# TOP_LEVEL.net
KiCad netlist of a schematic drawn in Altium Designer
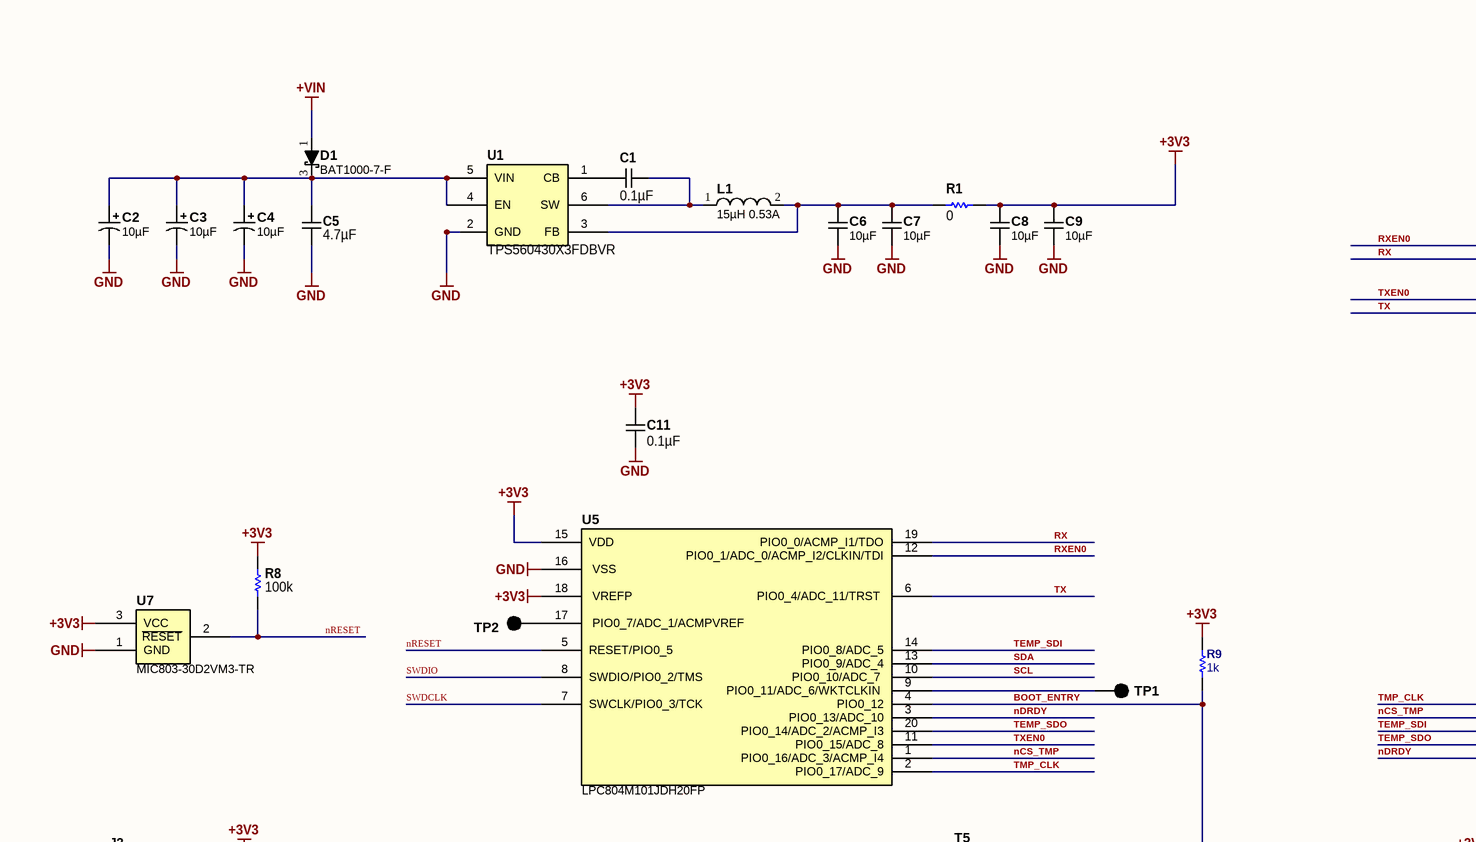
[diagram p0: TOP_LEVEL.SCHDOC, top left]
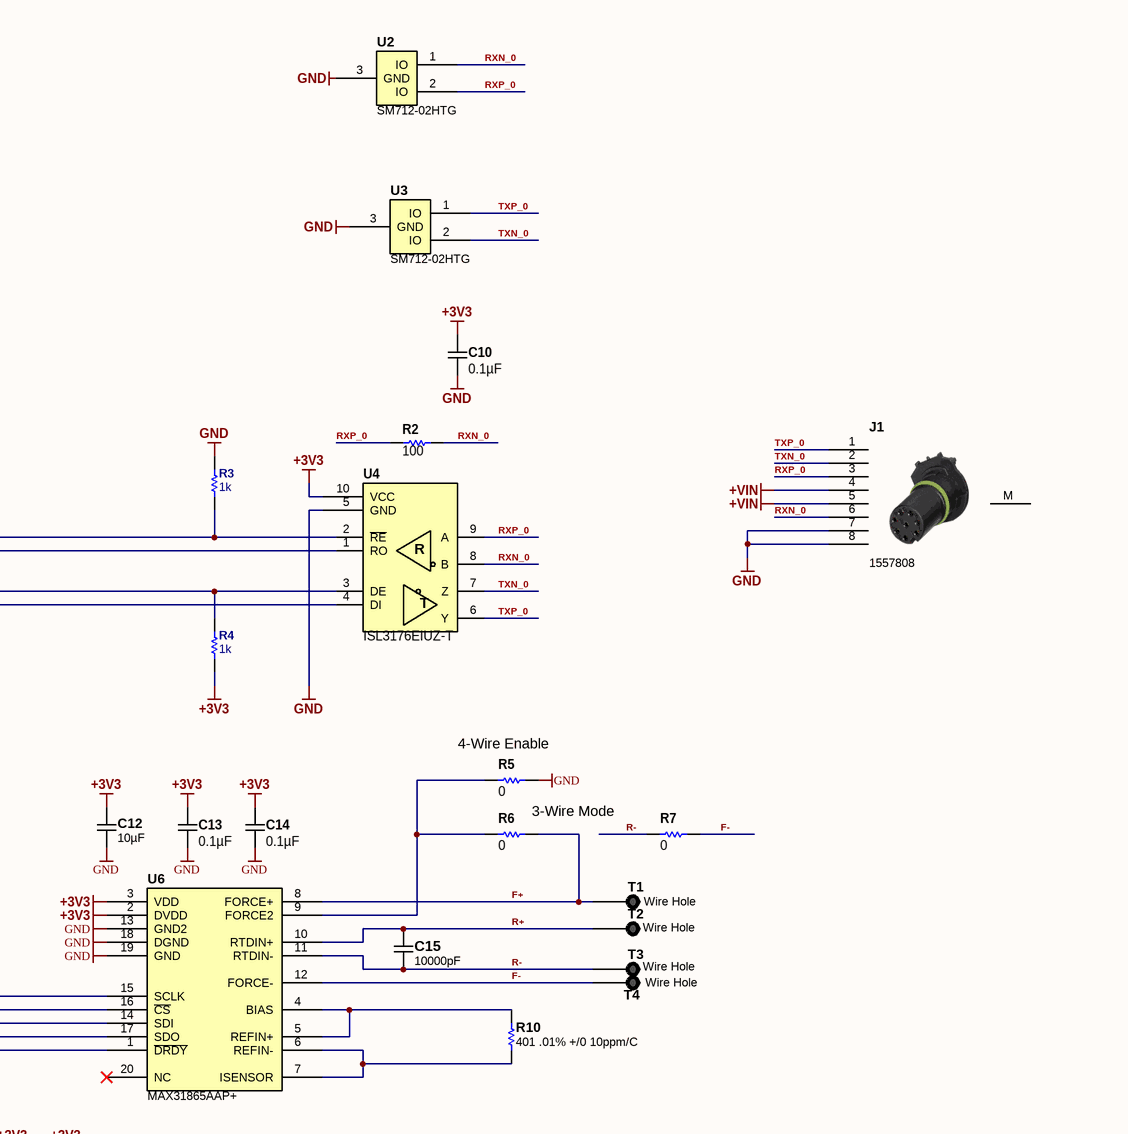
[diagram p1: TOP_LEVEL.SCHDOC, top right]
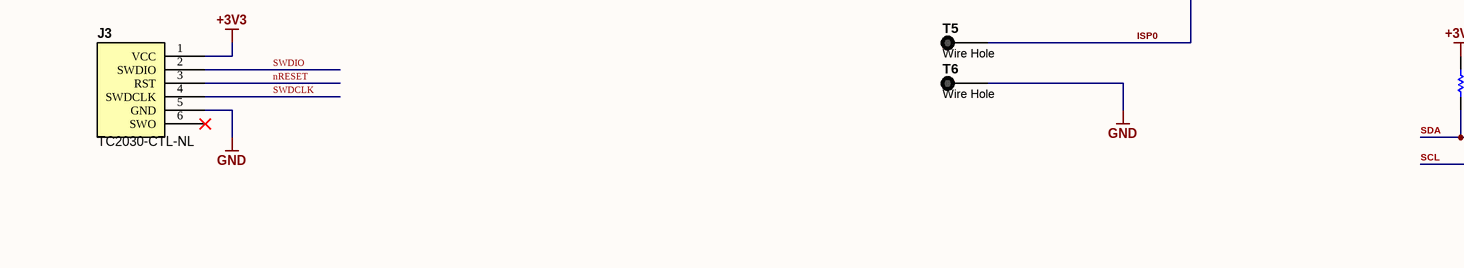
[diagram p2: TOP_LEVEL.SCHDOC, bottom left]
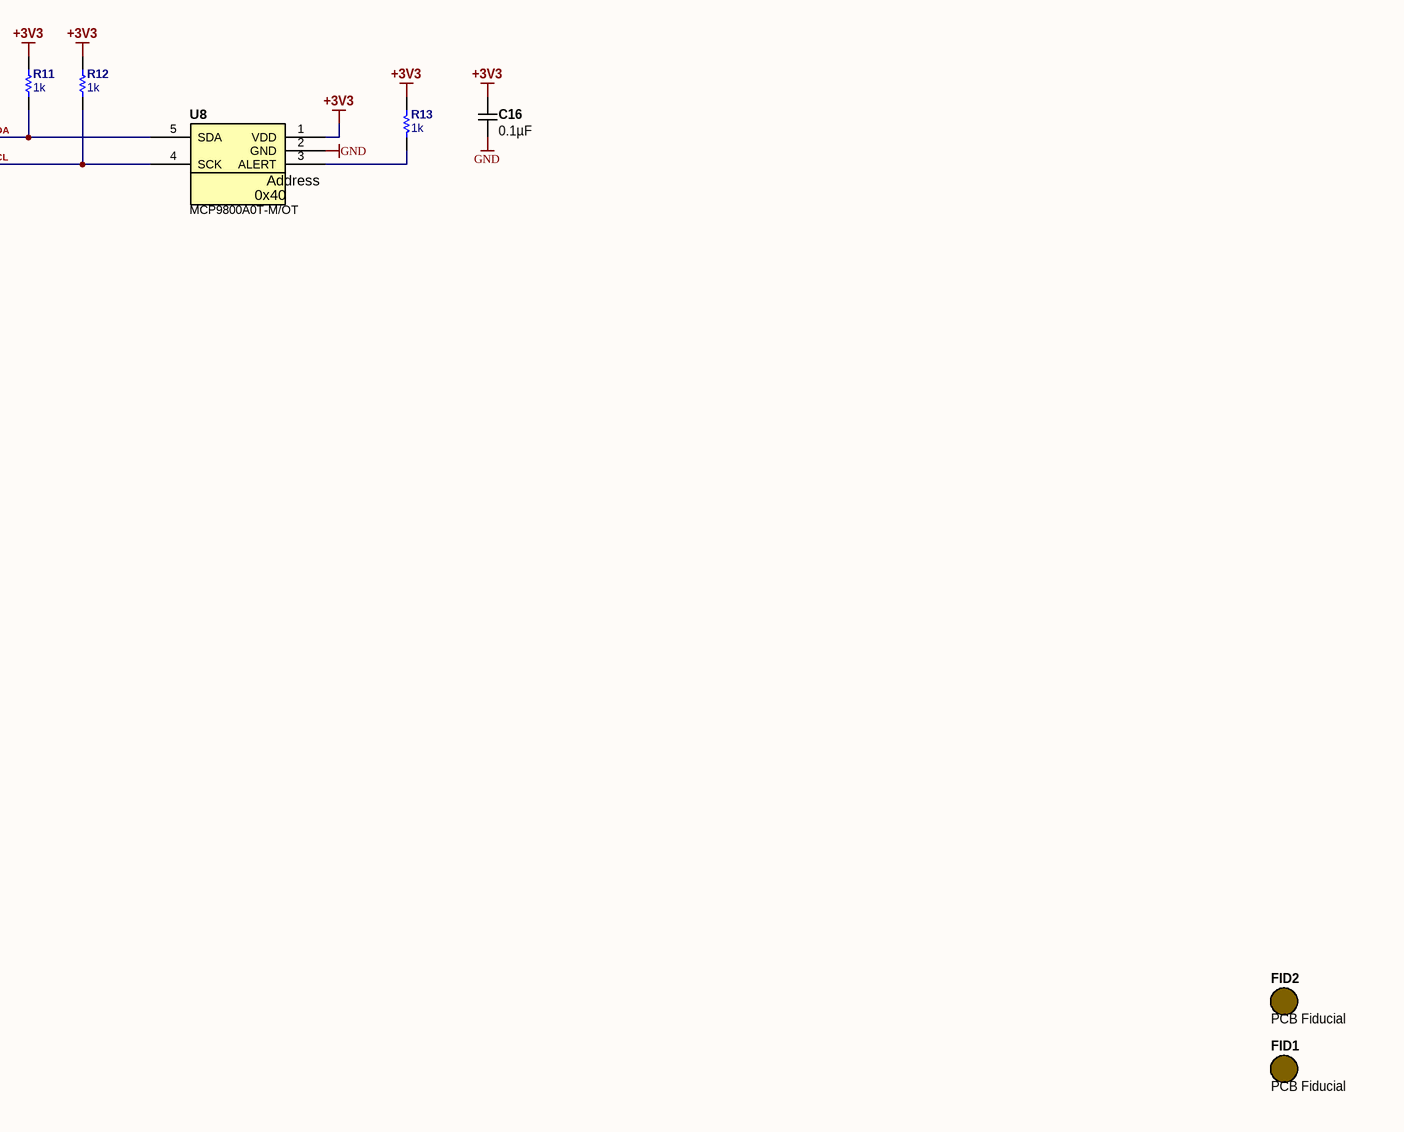
[diagram p3: TOP_LEVEL.SCHDOC, bottom right]

(export (version "E")
  (design (tool "Eeschema 10.0.6"))
  (components
    (comp (ref "C1")
      (value "0.1µF")
      (footprint "C0603_0.90MM_MD")
      (description "CAP CER 0.1UF 50V X7R 0603")
      (fields
        (field (name "MANUFACTURER PART NUMBER") "CGA3E2X7R1H104K080AE")
        (field (name "MANUFACTURER") "TDK Corporation")
      )
      (libsource (lib "Capacitors - TDK- AEC-Q200") (part "C_2P_NP"))
    )
    (comp (ref "C2")
      (value "10µF")
      (footprint "C_ALU_B")
      (description "CAP ALUM 10UF 35V 20% SMD")
      (fields
        (field (name "MANUFACTURER PART NUMBER") "EEE-FK1V100UR")
        (field (name "MANUFACTURER") "Panasonic Electronic Components")
      )
      (libsource (lib "Capacitors - Panasonic - AluminumElectrolytic - AEC-Q200") (part "C_2P_P"))
    )
    (comp (ref "C3")
      (value "10µF")
      (footprint "C_ALU_B")
      (description "CAP ALUM 10UF 35V 20% SMD")
      (fields
        (field (name "MANUFACTURER PART NUMBER") "EEE-FK1V100UR")
        (field (name "MANUFACTURER") "Panasonic Electronic Components")
      )
      (libsource (lib "Capacitors - Panasonic - AluminumElectrolytic - AEC-Q200") (part "C_2P_P"))
    )
    (comp (ref "C4")
      (value "10µF")
      (footprint "C_ALU_B")
      (description "CAP ALUM 10UF 35V 20% SMD")
      (fields
        (field (name "MANUFACTURER PART NUMBER") "EEE-FK1V100UR")
        (field (name "MANUFACTURER") "Panasonic Electronic Components")
      )
      (libsource (lib "Capacitors - Panasonic - AluminumElectrolytic - AEC-Q200") (part "C_2P_P"))
    )
    (comp (ref "C5")
      (value "4.7µF")
      (footprint "C0805_1.50MM_MD")
      (description "CAP CER 4.7UF 35V X7R 0805")
      (fields
        (field (name "MANUFACTURER PART NUMBER") "CGA4J1X7R1V475K125AE")
        (field (name "MANUFACTURER") "TDK Corporation")
      )
      (libsource (lib "Capacitors - TDK- AEC-Q200") (part "C_2P_NP"))
    )
    (comp (ref "C6")
      (value "10µF")
      (footprint "C0805_1.25MM_MD")
      (description "CAP CER 10UF 6.3V X7R 0805")
      (fields
        (field (name "MANUFACTURER PART NUMBER") "CGA4J1X7R0J106K125AD")
        (field (name "MANUFACTURER") "TDK Corporation")
      )
      (libsource (lib "Capacitors - TDK- AEC-Q200") (part "C_2P_NP"))
    )
    (comp (ref "C7")
      (value "10µF")
      (footprint "C0805_1.25MM_MD")
      (description "CAP CER 10UF 6.3V X7R 0805")
      (fields
        (field (name "MANUFACTURER PART NUMBER") "CGA4J1X7R0J106K125AD")
        (field (name "MANUFACTURER") "TDK Corporation")
      )
      (libsource (lib "Capacitors - TDK- AEC-Q200") (part "C_2P_NP"))
    )
    (comp (ref "C8")
      (value "10µF")
      (footprint "C0805_1.25MM_MD")
      (description "CAP CER 10UF 6.3V X7R 0805")
      (fields
        (field (name "MANUFACTURER PART NUMBER") "CGA4J1X7R0J106K125AD")
        (field (name "MANUFACTURER") "TDK Corporation")
      )
      (libsource (lib "Capacitors - TDK- AEC-Q200") (part "C_2P_NP"))
    )
    (comp (ref "C9")
      (value "10µF")
      (footprint "C0805_1.25MM_MD")
      (description "CAP CER 10UF 6.3V X7R 0805")
      (fields
        (field (name "MANUFACTURER PART NUMBER") "CGA4J1X7R0J106K125AD")
        (field (name "MANUFACTURER") "TDK Corporation")
      )
      (libsource (lib "Capacitors - TDK- AEC-Q200") (part "C_2P_NP"))
    )
    (comp (ref "C10")
      (value "0.1µF")
      (footprint "C0603_0.90MM_MD")
      (description "CAP CER 0.1UF 50V X7R 0603")
      (fields
        (field (name "MANUFACTURER PART NUMBER") "CGA3E2X7R1H104K080AE")
        (field (name "MANUFACTURER") "TDK Corporation")
      )
      (libsource (lib "Capacitors - TDK- AEC-Q200") (part "C_2P_NP"))
    )
    (comp (ref "C11")
      (value "0.1µF")
      (footprint "C0603_0.90MM_MD")
      (description "CAP CER 0.1UF 50V X7R 0603")
      (fields
        (field (name "MANUFACTURER PART NUMBER") "CGA3E2X7R1H104K080AE")
        (field (name "MANUFACTURER") "TDK Corporation")
      )
      (libsource (lib "Capacitors - TDK- AEC-Q200") (part "C_2P_NP"))
    )
    (comp (ref "C12")
      (value "10µF")
      (footprint "C0805_1.25MM_MD")
      (description "CAP CER 10UF 6.3V X7R 0805")
      (fields
        (field (name "MANUFACTURER PART NUMBER") "CGA4J1X7R0J106K125AD")
        (field (name "MANUFACTURER") "TDK Corporation")
      )
      (libsource (lib "Capacitors - TDK- AEC-Q200") (part "C_2P_NP"))
    )
    (comp (ref "C13")
      (value "0.1µF")
      (footprint "C0603_0.90MM_MD")
      (description "CAP CER 0.1UF 50V X7R 0603")
      (fields
        (field (name "MANUFACTURER PART NUMBER") "CGA3E2X7R1H104K080AE")
        (field (name "MANUFACTURER") "TDK Corporation")
      )
      (libsource (lib "Capacitors - TDK- AEC-Q200") (part "C_2P_NP"))
    )
    (comp (ref "C14")
      (value "0.1µF")
      (footprint "C0603_0.90MM_MD")
      (description "CAP CER 0.1UF 50V X7R 0603")
      (fields
        (field (name "MANUFACTURER PART NUMBER") "CGA3E2X7R1H104K080AE")
        (field (name "MANUFACTURER") "TDK Corporation")
      )
      (libsource (lib "Capacitors - TDK- AEC-Q200") (part "C_2P_NP"))
    )
    (comp (ref "C15")
      (value "10000pF")
      (footprint "C0603_0.90MM_HD")
      (description "CAP CER 10000PF 50V X7R 0603")
      (fields
        (field (name "MANUFACTURER PART NUMBER") "AC0603KPX7R9BB103")
        (field (name "MANUFACTURER") "Yageo")
      )
      (libsource (lib "Capacitors - Yageo - AEC-Q200") (part "C_2P_NP"))
    )
    (comp (ref "C16")
      (value "0.1µF")
      (footprint "C0603_0.90MM_MD")
      (description "CAP CER 0.1UF 50V X7R 0603")
      (fields
        (field (name "MANUFACTURER PART NUMBER") "CGA3E2X7R1H104K080AE")
        (field (name "MANUFACTURER") "TDK Corporation")
      )
      (libsource (lib "Capacitors - TDK- AEC-Q200") (part "C_2P_NP"))
    )
    (comp (ref "D1")
      (value "BAT1000-7-F")
      (footprint "D_SOT-23-3_P")
      (description "DIODE SCHOTTKY 40V 1A SOT23")
      (fields (field (name "MANUFACTURER") "Diodes Inc"))
      (libsource (lib "Diodes") (part "DS_1A_3C"))
    )
    (comp (ref "FID1")
      (value "PCB Fiducial")
      (footprint "Fiducial 1mm - 2mm")
      (libsource (lib "eFiducial") (part "Fiducial"))
    )
    (comp (ref "FID2")
      (value "PCB Fiducial")
      (footprint "Fiducial 1mm - 2mm")
      (libsource (lib "eFiducial") (part "Fiducial"))
    )
    (comp (ref "J1")
      (value "1557808")
      (footprint "1557808")
      (description "Circular Metric Connectors SACC-CI-M12FS -8CON-L180-THR")
      (fields (field (name "MANUFACTURER") "Phoenix Contact"))
      (libsource (lib "eConnector_Phoenix_M12") (part "1557808"))
    )
    (comp (ref "J3")
      (value "TC2030‐CTL‐NL")
      (footprint "TC2030")
      (description "Tag Connect Pads - No latching Clips - ARM")
      (libsource (lib "eConnector") (part "TC2030‐CTL‐NL"))
    )
    (comp (ref "L1")
      (value "15µH 0.53A")
      (footprint "L_NRH3012")
      (description "Inductor 15µH 0.53A")
      (fields
        (field (name "MANUFACTURER PART NUMBER") "NRH3012T150MN")
        (field (name "MANUFACTURER") "Taiyo Yuden")
      )
      (libsource (lib "Inductors") (part "L_2P"))
    )
    (comp (ref "R1")
      (value "0")
      (footprint "R0603_0.55MM_MD")
      (description "RES 0.0 OHM 1/10W JUMP 0603 SMD")
      (fields
        (field (name "MANUFACTURER PART NUMBER") "ERJ-3GEY0R00V")
        (field (name "MANUFACTURER") "Panasonic Electronic Components")
      )
      (libsource (lib "Resistors - Panasonic - AEC-Q200") (part "R_2P"))
    )
    (comp (ref "R2")
      (value "100")
      (footprint "R0603_0.55MM_MD")
      (description "RES 100 OHM 1/10W 1% 0603 SMD")
      (fields
        (field (name "MANUFACTURER PART NUMBER") "ERJ-3EKF1000V")
        (field (name "MANUFACTURER") "Panasonic Electronic Components")
      )
      (libsource (lib "Resistors - Panasonic - AEC-Q200") (part "R_2P"))
    )
    (comp (ref "R3")
      (value "1k")
      (footprint "R0603_0.55MM_MD")
      (description "RES 1K OHM 1/10W 1% 0603 SMD")
      (fields
        (field (name "MANUFACTURER PART NUMBER") "ERJ-3EKF1001V")
        (field (name "MANUFACTURER") "Panasonic Electronic Components")
      )
      (libsource (lib "Resistors - Panasonic - AEC-Q200") (part "R_2P"))
    )
    (comp (ref "R4")
      (value "1k")
      (footprint "R0603_0.55MM_MD")
      (description "RES 1K OHM 1/10W 1% 0603 SMD")
      (fields
        (field (name "MANUFACTURER PART NUMBER") "ERJ-3EKF1001V")
        (field (name "MANUFACTURER") "Panasonic Electronic Components")
      )
      (libsource (lib "Resistors - Panasonic - AEC-Q200") (part "R_2P"))
    )
    (comp (ref "R5")
      (value "0")
      (footprint "R0603_0.55MM_MD")
      (description "RES 0.0 OHM 1/10W JUMP 0603 SMD")
      (fields
        (field (name "MANUFACTURER PART NUMBER") "ERJ-3GEY0R00V")
        (field (name "MANUFACTURER") "Panasonic Electronic Components")
      )
      (libsource (lib "Resistors - Panasonic - AEC-Q200") (part "R_2P"))
    )
    (comp (ref "R6")
      (value "0")
      (footprint "R0603_0.55MM_MD")
      (description "RES 0.0 OHM 1/10W JUMP 0603 SMD")
      (fields
        (field (name "MANUFACTURER PART NUMBER") "ERJ-3GEY0R00V")
        (field (name "MANUFACTURER") "Panasonic Electronic Components")
      )
      (libsource (lib "Resistors - Panasonic - AEC-Q200") (part "R_2P"))
    )
    (comp (ref "R7")
      (value "0")
      (footprint "R0603_0.55MM_MD")
      (description "RES 0.0 OHM 1/10W JUMP 0603 SMD")
      (fields
        (field (name "MANUFACTURER PART NUMBER") "ERJ-3GEY0R00V")
        (field (name "MANUFACTURER") "Panasonic Electronic Components")
      )
      (libsource (lib "Resistors - Panasonic - AEC-Q200") (part "R_2P"))
    )
    (comp (ref "R8")
      (value "100k")
      (footprint "R0603_0.55MM_MD")
      (description "RES 100K OHM 1/10W 1% 0603 SMD")
      (fields
        (field (name "MANUFACTURER PART NUMBER") "ERJ-3EKF1003V")
        (field (name "MANUFACTURER") "Panasonic Electronic Components")
      )
      (libsource (lib "Resistors - Panasonic - AEC-Q200") (part "R_2P"))
    )
    (comp (ref "R9")
      (value "1k")
      (footprint "R0603_0.55MM_MD")
      (description "RES 1K OHM 1/10W 1% 0603 SMD")
      (fields
        (field (name "MANUFACTURER PART NUMBER") "ERJ-3EKF1001V")
        (field (name "MANUFACTURER") "Panasonic Electronic Components")
      )
      (libsource (lib "Resistors - Panasonic - AEC-Q200") (part "R_2P"))
    )
    (comp (ref "R10")
      (value "401 .01% +/0 10ppm/C")
      (footprint "R0603_0.55MM_MD")
      (description "402 ±0.1% 0.15W Chip Resistor 0603 (1608 Metric) Anti-Sulfur, Automotive AEC-Q200 Thin Film")
      (fields
        (field (name "MANUFACTURER") "TE Connectivity")
        (field (name "MANUFACTURER PART NUMBER") "RQ73C1J402RBTD")
      )
      (libsource (lib "eResistors") (part "RQ73C1J402RBTD"))
    )
    (comp (ref "R11")
      (value "1k")
      (footprint "R0603_0.55MM_MD")
      (description "RES 1K OHM 1/10W 1% 0603 SMD")
      (fields
        (field (name "MANUFACTURER PART NUMBER") "ERJ-3EKF1001V")
        (field (name "MANUFACTURER") "Panasonic Electronic Components")
      )
      (libsource (lib "Resistors - Panasonic - AEC-Q200") (part "R_2P"))
    )
    (comp (ref "R12")
      (value "1k")
      (footprint "R0603_0.55MM_MD")
      (description "RES 1K OHM 1/10W 1% 0603 SMD")
      (fields
        (field (name "MANUFACTURER PART NUMBER") "ERJ-3EKF1001V")
        (field (name "MANUFACTURER") "Panasonic Electronic Components")
      )
      (libsource (lib "Resistors - Panasonic - AEC-Q200") (part "R_2P"))
    )
    (comp (ref "R13")
      (value "1k")
      (footprint "R0603_0.55MM_MD")
      (description "RES 1K OHM 1/10W 1% 0603 SMD")
      (fields
        (field (name "MANUFACTURER PART NUMBER") "ERJ-3EKF1001V")
        (field (name "MANUFACTURER") "Panasonic Electronic Components")
      )
      (libsource (lib "Resistors - Panasonic - AEC-Q200") (part "R_2P"))
    )
    (comp (ref "T1")
      (value "Wire Hole")
      (footprint "SOLDER_HOLE")
      (libsource (lib "eConnector") (part "SOLDER_HOLE"))
    )
    (comp (ref "T2")
      (value "Wire Hole")
      (footprint "SOLDER_HOLE")
      (libsource (lib "eConnector") (part "SOLDER_HOLE"))
    )
    (comp (ref "T3")
      (value "Wire Hole")
      (footprint "SOLDER_HOLE")
      (libsource (lib "eConnector") (part "SOLDER_HOLE"))
    )
    (comp (ref "T4")
      (value "Wire Hole")
      (footprint "SOLDER_HOLE")
      (libsource (lib "eConnector") (part "SOLDER_HOLE"))
    )
    (comp (ref "T5")
      (value "Wire Hole")
      (footprint "SOLDER_HOLE")
      (libsource (lib "eConnector") (part "SOLDER_HOLE"))
    )
    (comp (ref "T6")
      (value "Wire Hole")
      (footprint "SOLDER_HOLE")
      (libsource (lib "eConnector") (part "SOLDER_HOLE"))
    )
    (comp (ref "TP1")
      (value "SMT_TEST")
      (footprint "SMT_TP - 35")
      (libsource (lib "eTestPoint") (part "SMT_TEST"))
    )
    (comp (ref "TP2")
      (value "SMT_TEST")
      (footprint "SMT_TP - 35")
      (libsource (lib "eTestPoint") (part "SMT_TEST"))
    )
    (comp (ref "U1")
      (value "TPS560430X3FDBVR")
      (footprint "SOT95P245X145-6L")
      (description "Buck Switching Regulator IC Positive PWM 3.3V 1 Output 600mA SOT-23-6")
      (fields (field (name "MANUFACTURER") "Texas Instruments"))
      (libsource (lib "eIC_Regulator") (part "TPS560430X3FDBVR"))
    )
    (comp (ref "U2")
      (value "SM712-02HTG")
      (footprint "SOT-23")
      (fields (field (name "MANUFACTURER") "Littelfuse"))
      (libsource (lib "eDiode") (part "SM712-02HTG"))
    )
    (comp (ref "U3")
      (value "SM712-02HTG")
      (footprint "SOT-23")
      (fields (field (name "MANUFACTURER") "Littelfuse"))
      (libsource (lib "eDiode") (part "SM712-02HTG"))
    )
    (comp (ref "U4")
      (value "ISL3176EIUZ-T")
      (footprint "10 MSOP")
      (description "IC TXRX RS422/485 20MBPS 10MSOP")
      (fields (field (name "MANUFACTURER") "Intersil"))
      (libsource (lib "eIC") (part "ISL3176EIUZ-T"))
    )
    (comp (ref "U5")
      (value "LPC804M101JDH20FP")
      (footprint "TSOP65P640X105-20N")
      (description "MCU 32-bit ARM Cortex M0+ RISC 32KB Flash 3.3V 20-Pin TSSOP Tube")
      (fields (field (name "MANUFACTURER") "NXP Semiconductors"))
      (libsource (lib "eIC") (part "LPC804M101JDH20FP"))
    )
    (comp (ref "U6")
      (value "MAX31865AAP+")
      (footprint "SOP65P780X200-20N")
      (description "Temp Monitoring System (Sensor)  External Sensor SPI Output 20-SSOP")
      (fields (field (name "MANUFACTURER") "Maxim"))
      (libsource (lib "eIC") (part "MAX31865AAP+"))
    )
    (comp (ref "U7")
      (value "MIC803-30D2VM3-TR")
      (footprint "SOT-23")
      (description "3-Pin Microprocessor Supervisor Circuit w/ Open-Drain Reset Output, 3 SOT-23 - T/R")
      (fields (field (name "MANUFACTURER") "Microchip"))
      (libsource (lib "eIC") (part "MIC803-30D2VM3-TR"))
    )
    (comp (ref "U8")
      (value "MCP9800A0T-M/OT")
      (footprint "SOT23-5")
      (description "SENSOR TEMP I2C/SMBUS SOT23-5")
      (fields (field (name "MANUFACTURER") "Microchip Technology"))
      (libsource (lib "eIC") (part "MCP9800A0T-M/OT"))
    )
  )
  (nets
    (net (code "1") (name "+3V3") (class "Default")
      (node (ref "C10") (pin "2") (pinfunction "1_2") (pintype "passive"))
      (node (ref "C11") (pin "2") (pinfunction "1_2") (pintype "passive"))
      (node (ref "C12") (pin "2") (pinfunction "1_2") (pintype "passive"))
      (node (ref "C13") (pin "2") (pinfunction "1_2") (pintype "passive"))
      (node (ref "C14") (pin "2") (pinfunction "1_2") (pintype "passive"))
      (node (ref "C16") (pin "2") (pinfunction "1_2") (pintype "passive"))
      (node (ref "C8") (pin "2") (pinfunction "1_2") (pintype "passive"))
      (node (ref "C9") (pin "2") (pinfunction "1_2") (pintype "passive"))
      (node (ref "J3") (pin "1") (pinfunction "VCC_1") (pintype "passive"))
      (node (ref "R1") (pin "2") (pinfunction "2_2") (pintype "passive"))
      (node (ref "R11") (pin "1") (pinfunction "1_1") (pintype "passive"))
      (node (ref "R12") (pin "1") (pinfunction "1_1") (pintype "passive"))
      (node (ref "R13") (pin "1") (pinfunction "1_1") (pintype "passive"))
      (node (ref "R4") (pin "2") (pinfunction "2_2") (pintype "passive"))
      (node (ref "R8") (pin "1") (pinfunction "1_1") (pintype "passive"))
      (node (ref "R9") (pin "1") (pinfunction "1_1") (pintype "passive"))
      (node (ref "U4") (pin "10") (pinfunction "VCC_10") (pintype "passive"))
      (node (ref "U5") (pin "15") (pinfunction "VDD_15") (pintype "passive"))
      (node (ref "U5") (pin "18") (pinfunction "_VREFP_18") (pintype "passive"))
      (node (ref "U6") (pin "2") (pinfunction "DVDD_2") (pintype "passive"))
      (node (ref "U6") (pin "3") (pinfunction "VDD_3") (pintype "passive"))
      (node (ref "U7") (pin "3") (pinfunction "VCC_3") (pintype "passive"))
      (node (ref "U8") (pin "1") (pinfunction "VDD_1") (pintype "passive"))
    )
    (net (code "2") (name "+VIN") (class "Default")
      (node (ref "D1") (pin "1") (pinfunction "A_1") (pintype "passive"))
      (node (ref "J1") (pin "4") (pinfunction "4_4") (pintype "passive"))
      (node (ref "J1") (pin "5") (pinfunction "5_5") (pintype "passive"))
    )
    (net (code "3") (name "/BOOT_ENTRY") (class "Default")
      (node (ref "R9") (pin "2") (pinfunction "2_2") (pintype "passive"))
      (node (ref "T5") (pin "1") (pinfunction "1_1") (pintype "passive"))
      (node (ref "U5") (pin "4") (pinfunction "PIO0_12_4") (pintype "passive"))
    )
    (net (code "4") (name "/F+") (class "Default")
      (node (ref "R6") (pin "2") (pinfunction "2_2") (pintype "passive"))
      (node (ref "T1") (pin "1") (pinfunction "1_1") (pintype "passive"))
      (node (ref "U6") (pin "8") (pinfunction "FORCE+_8") (pintype "passive"))
    )
    (net (code "5") (name "/F-") (class "Default")
      (node (ref "R7") (pin "2") (pinfunction "2_2") (pintype "passive"))
      (node (ref "T4") (pin "1") (pinfunction "1_1") (pintype "passive"))
      (node (ref "U6") (pin "12") (pinfunction "FORCE-_12") (pintype "passive"))
    )
    (net (code "6") (name "/R+") (class "Default")
      (node (ref "C15") (pin "2") (pinfunction "1_2") (pintype "passive"))
      (node (ref "T2") (pin "1") (pinfunction "1_1") (pintype "passive"))
      (node (ref "U6") (pin "10") (pinfunction "RTDIN+_10") (pintype "passive"))
    )
    (net (code "7") (name "/R-") (class "Default")
      (node (ref "C15") (pin "1") (pinfunction "1_1") (pintype "passive"))
      (node (ref "R7") (pin "1") (pinfunction "1_1") (pintype "passive"))
      (node (ref "T3") (pin "1") (pinfunction "1_1") (pintype "passive"))
      (node (ref "U6") (pin "11") (pinfunction "RTDIN-_11") (pintype "passive"))
    )
    (net (code "8") (name "/RX") (class "Default")
      (node (ref "U4") (pin "1") (pinfunction "RO_1") (pintype "passive"))
      (node (ref "U5") (pin "19") (pinfunction "_PIO0_0/ACMP_I1/TDO_19") (pintype "passive"))
    )
    (net (code "9") (name "/RXEN0") (class "Default")
      (node (ref "R3") (pin "2") (pinfunction "2_2") (pintype "passive"))
      (node (ref "U4") (pin "2") (pinfunction "~{RE}_2") (pintype "passive"))
      (node (ref "U5") (pin "12") (pinfunction "PIO0_1/ADC_0/ACMP_I2/CLKIN/TDI_12") (pintype "passive"))
    )
    (net (code "10") (name "/RXN_0") (class "Default")
      (node (ref "J1") (pin "6") (pinfunction "6_6") (pintype "passive"))
      (node (ref "R2") (pin "2") (pinfunction "2_2") (pintype "passive"))
      (node (ref "U2") (pin "1") (pinfunction "IO_1") (pintype "passive"))
      (node (ref "U4") (pin "8") (pinfunction "B_8") (pintype "passive"))
    )
    (net (code "11") (name "/RXP_0") (class "Default")
      (node (ref "J1") (pin "3") (pinfunction "3_3") (pintype "passive"))
      (node (ref "R2") (pin "1") (pinfunction "1_1") (pintype "passive"))
      (node (ref "U2") (pin "2") (pinfunction "IO_2") (pintype "passive"))
      (node (ref "U4") (pin "9") (pinfunction "A_9") (pintype "passive"))
    )
    (net (code "12") (name "/SCL") (class "Default")
      (node (ref "R12") (pin "2") (pinfunction "2_2") (pintype "passive"))
      (node (ref "U5") (pin "10") (pinfunction "PIO0_10/ADC_7_10") (pintype "passive"))
      (node (ref "U8") (pin "4") (pinfunction "SCK_4") (pintype "passive"))
    )
    (net (code "13") (name "/SDA") (class "Default")
      (node (ref "R11") (pin "2") (pinfunction "2_2") (pintype "passive"))
      (node (ref "U5") (pin "13") (pinfunction "PIO0_9/ADC_4_13") (pintype "passive"))
      (node (ref "U8") (pin "5") (pinfunction "SDA_5") (pintype "passive"))
    )
    (net (code "14") (name "/SWDCLK") (class "Default")
      (node (ref "J3") (pin "4") (pinfunction "SWDCLK_4") (pintype "passive"))
      (node (ref "U5") (pin "7") (pinfunction "SWCLK/PIO0_3/TCK_7") (pintype "passive"))
    )
    (net (code "15") (name "/SWDIO") (class "Default")
      (node (ref "J3") (pin "2") (pinfunction "SWDIO_2") (pintype "passive"))
      (node (ref "U5") (pin "8") (pinfunction "SWDIO/PIO0_2/TMS_8") (pintype "passive"))
    )
    (net (code "16") (name "/TEMP_SDI") (class "Default")
      (node (ref "U5") (pin "14") (pinfunction "PIO0_8/ADC_5_14") (pintype "passive"))
      (node (ref "U6") (pin "14") (pinfunction "SDI_14") (pintype "passive"))
    )
    (net (code "17") (name "/TEMP_SDO") (class "Default")
      (node (ref "U5") (pin "20") (pinfunction "_PIO0_14/ADC_2/ACMP_I3_20") (pintype "passive"))
      (node (ref "U6") (pin "17") (pinfunction "SDO_17") (pintype "passive"))
    )
    (net (code "18") (name "/TMP_CLK") (class "Default")
      (node (ref "U5") (pin "2") (pinfunction "PIO0_17/ADC_9_2") (pintype "passive"))
      (node (ref "U6") (pin "15") (pinfunction "SCLK_15") (pintype "passive"))
    )
    (net (code "19") (name "/TX") (class "Default")
      (node (ref "U4") (pin "4") (pinfunction "DI_4") (pintype "passive"))
      (node (ref "U5") (pin "6") (pinfunction "PIO0_4/ADC_11/TRST_6") (pintype "passive"))
    )
    (net (code "20") (name "/TXEN0") (class "Default")
      (node (ref "R4") (pin "1") (pinfunction "1_1") (pintype "passive"))
      (node (ref "U4") (pin "3") (pinfunction "DE_3") (pintype "passive"))
      (node (ref "U5") (pin "11") (pinfunction "PIO0_15/ADC_8_11") (pintype "passive"))
    )
    (net (code "21") (name "/TXN_0") (class "Default")
      (node (ref "J1") (pin "2") (pinfunction "2_2") (pintype "passive"))
      (node (ref "U3") (pin "2") (pinfunction "IO_2") (pintype "passive"))
      (node (ref "U4") (pin "7") (pinfunction "Z_7") (pintype "passive"))
    )
    (net (code "22") (name "/TXP_0") (class "Default")
      (node (ref "J1") (pin "1") (pinfunction "1_1") (pintype "passive"))
      (node (ref "U3") (pin "1") (pinfunction "IO_1") (pintype "passive"))
      (node (ref "U4") (pin "6") (pinfunction "Y_6") (pintype "passive"))
    )
    (net (code "23") (name "/nCS_TMP") (class "Default")
      (node (ref "U5") (pin "1") (pinfunction "PIO0_16/ADC_3/ACMP_I4_1") (pintype "passive"))
      (node (ref "U6") (pin "16") (pinfunction "~{CS}_16") (pintype "passive"))
    )
    (net (code "24") (name "/nDRDY") (class "Default")
      (node (ref "U5") (pin "3") (pinfunction "PIO0_13/ADC_10_3") (pintype "passive"))
      (node (ref "U6") (pin "1") (pinfunction "~{DRDY}_1") (pintype "passive"))
    )
    (net (code "25") (name "/nRESET") (class "Default")
      (node (ref "J3") (pin "3") (pinfunction "RST_3") (pintype "passive"))
      (node (ref "R8") (pin "2") (pinfunction "2_2") (pintype "passive"))
      (node (ref "U5") (pin "5") (pinfunction "RESET/PIO0_5_5") (pintype "passive"))
      (node (ref "U7") (pin "2") (pinfunction "~{RESET}_2") (pintype "passive"))
    )
    (net (code "26") (name "GND") (class "Default")
      (node (ref "C10") (pin "1") (pinfunction "1_1") (pintype "passive"))
      (node (ref "C11") (pin "1") (pinfunction "1_1") (pintype "passive"))
      (node (ref "C12") (pin "1") (pinfunction "1_1") (pintype "passive"))
      (node (ref "C13") (pin "1") (pinfunction "1_1") (pintype "passive"))
      (node (ref "C14") (pin "1") (pinfunction "1_1") (pintype "passive"))
      (node (ref "C16") (pin "1") (pinfunction "1_1") (pintype "passive"))
      (node (ref "C2") (pin "2") (pinfunction "1_2") (pintype "passive"))
      (node (ref "C3") (pin "2") (pinfunction "1_2") (pintype "passive"))
      (node (ref "C4") (pin "2") (pinfunction "1_2") (pintype "passive"))
      (node (ref "C5") (pin "1") (pinfunction "1_1") (pintype "passive"))
      (node (ref "C6") (pin "1") (pinfunction "1_1") (pintype "passive"))
      (node (ref "C7") (pin "1") (pinfunction "1_1") (pintype "passive"))
      (node (ref "C8") (pin "1") (pinfunction "1_1") (pintype "passive"))
      (node (ref "C9") (pin "1") (pinfunction "1_1") (pintype "passive"))
      (node (ref "J1") (pin "7") (pinfunction "7_7") (pintype "passive"))
      (node (ref "J1") (pin "8") (pinfunction "8_8") (pintype "passive"))
      (node (ref "J3") (pin "5") (pinfunction "GND_5") (pintype "passive"))
      (node (ref "R3") (pin "1") (pinfunction "1_1") (pintype "passive"))
      (node (ref "R5") (pin "2") (pinfunction "2_2") (pintype "passive"))
      (node (ref "T6") (pin "1") (pinfunction "1_1") (pintype "passive"))
      (node (ref "U1") (pin "2") (pinfunction "GND_2") (pintype "passive"))
      (node (ref "U3") (pin "3") (pinfunction "GND_3") (pintype "passive"))
      (node (ref "U4") (pin "5") (pinfunction "GND_5") (pintype "passive"))
      (node (ref "U5") (pin "16") (pinfunction "_VSS_16") (pintype "passive"))
      (node (ref "U6") (pin "13") (pinfunction "GND2_13") (pintype "passive"))
      (node (ref "U6") (pin "18") (pinfunction "DGND_18") (pintype "passive"))
      (node (ref "U6") (pin "19") (pinfunction "GND_19") (pintype "passive"))
      (node (ref "U7") (pin "1") (pinfunction "GND_1") (pintype "passive"))
      (node (ref "U8") (pin "2") (pinfunction "GND_2") (pintype "passive"))
    )
    (net (code "27") (name "Net-(D1-K)") (class "Default")
      (node (ref "C2") (pin "1") (pinfunction "1_1") (pintype "passive"))
      (node (ref "C3") (pin "1") (pinfunction "1_1") (pintype "passive"))
      (node (ref "C4") (pin "1") (pinfunction "1_1") (pintype "passive"))
      (node (ref "C5") (pin "2") (pinfunction "1_2") (pintype "passive"))
      (node (ref "D1") (pin "3") (pinfunction "K_3") (pintype "passive"))
      (node (ref "U1") (pin "4") (pinfunction "EN_4") (pintype "passive"))
      (node (ref "U1") (pin "5") (pinfunction "VIN_5") (pintype "passive"))
    )
    (net (code "28") (name "Net-(U1-CB)") (class "Default")
      (node (ref "C1") (pin "2") (pinfunction "1_2") (pintype "passive"))
      (node (ref "U1") (pin "1") (pinfunction "CB_1") (pintype "passive"))
    )
    (net (code "29") (name "Net-(U1-FB)") (class "Default")
      (node (ref "C6") (pin "2") (pinfunction "1_2") (pintype "passive"))
      (node (ref "C7") (pin "2") (pinfunction "1_2") (pintype "passive"))
      (node (ref "L1") (pin "2") (pinfunction "2_2") (pintype "passive"))
      (node (ref "R1") (pin "1") (pinfunction "1_1") (pintype "passive"))
      (node (ref "U1") (pin "3") (pinfunction "FB_3") (pintype "passive"))
    )
    (net (code "30") (name "Net-(U1-SW)") (class "Default")
      (node (ref "C1") (pin "1") (pinfunction "1_1") (pintype "passive"))
      (node (ref "L1") (pin "1") (pinfunction "1_1") (pintype "passive"))
      (node (ref "U1") (pin "6") (pinfunction "SW_6") (pintype "passive"))
    )
    (net (code "31") (name "Net-(U5-PIO0_11{slash}ADC_6{slash}WKTCLKIN)") (class "Default")
      (node (ref "TP1") (pin "1") (pinfunction "1_1") (pintype "passive"))
      (node (ref "U5") (pin "9") (pinfunction "PIO0_11/ADC_6/WKTCLKIN_9") (pintype "passive"))
    )
    (net (code "32") (name "Net-(U5-_PIO0_7{slash}ADC_1{slash}ACMPVREF)") (class "Default")
      (node (ref "TP2") (pin "1") (pinfunction "1_1") (pintype "passive"))
      (node (ref "U5") (pin "17") (pinfunction "_PIO0_7/ADC_1/ACMPVREF_17") (pintype "passive"))
    )
    (net (code "33") (name "Net-(U6-BIAS)") (class "Default")
      (node (ref "R10") (pin "2") (pinfunction "2_2") (pintype "passive"))
      (node (ref "U6") (pin "4") (pinfunction "BIAS_4") (pintype "passive"))
      (node (ref "U6") (pin "5") (pinfunction "REFIN+_5") (pintype "passive"))
    )
    (net (code "34") (name "Net-(U6-FORCE2)") (class "Default")
      (node (ref "R5") (pin "1") (pinfunction "1_1") (pintype "passive"))
      (node (ref "R6") (pin "1") (pinfunction "1_1") (pintype "passive"))
      (node (ref "U6") (pin "9") (pinfunction "FORCE2_9") (pintype "passive"))
    )
    (net (code "35") (name "Net-(U6-ISENSOR)") (class "Default")
      (node (ref "R10") (pin "1") (pinfunction "1_1") (pintype "passive"))
      (node (ref "U6") (pin "6") (pinfunction "REFIN-_6") (pintype "passive"))
      (node (ref "U6") (pin "7") (pinfunction "ISENSOR_7") (pintype "passive"))
    )
    (net (code "36") (name "Net-(U8-ALERT)") (class "Default")
      (node (ref "R13") (pin "2") (pinfunction "2_2") (pintype "passive"))
      (node (ref "U8") (pin "3") (pinfunction "ALERT_3") (pintype "passive"))
    )
    (net (code "37") (name "unconnected-(J1-PadM)") (class "Default")
      (node (ref "J1") (pin "M") (pinfunction "M_M") (pintype "passive"))
    )
    (net (code "38") (name "unconnected-(J3-SWO-Pad6)") (class "Default")
      (node (ref "J3") (pin "6") (pinfunction "SWO_6") (pintype "passive+no_connect"))
    )
    (net (code "39") (name "unconnected-(U2-GND-Pad3)") (class "Default")
      (node (ref "U2") (pin "3") (pinfunction "GND_3") (pintype "passive"))
    )
    (net (code "40") (name "unconnected-(U6-NC-Pad20)") (class "Default")
      (node (ref "U6") (pin "20") (pinfunction "NC_20") (pintype "passive+no_connect"))
    )
  )
)
